# AmbaSat-1_version_2_01.net
KiCad netlist of a schematic drawn in EAGLE
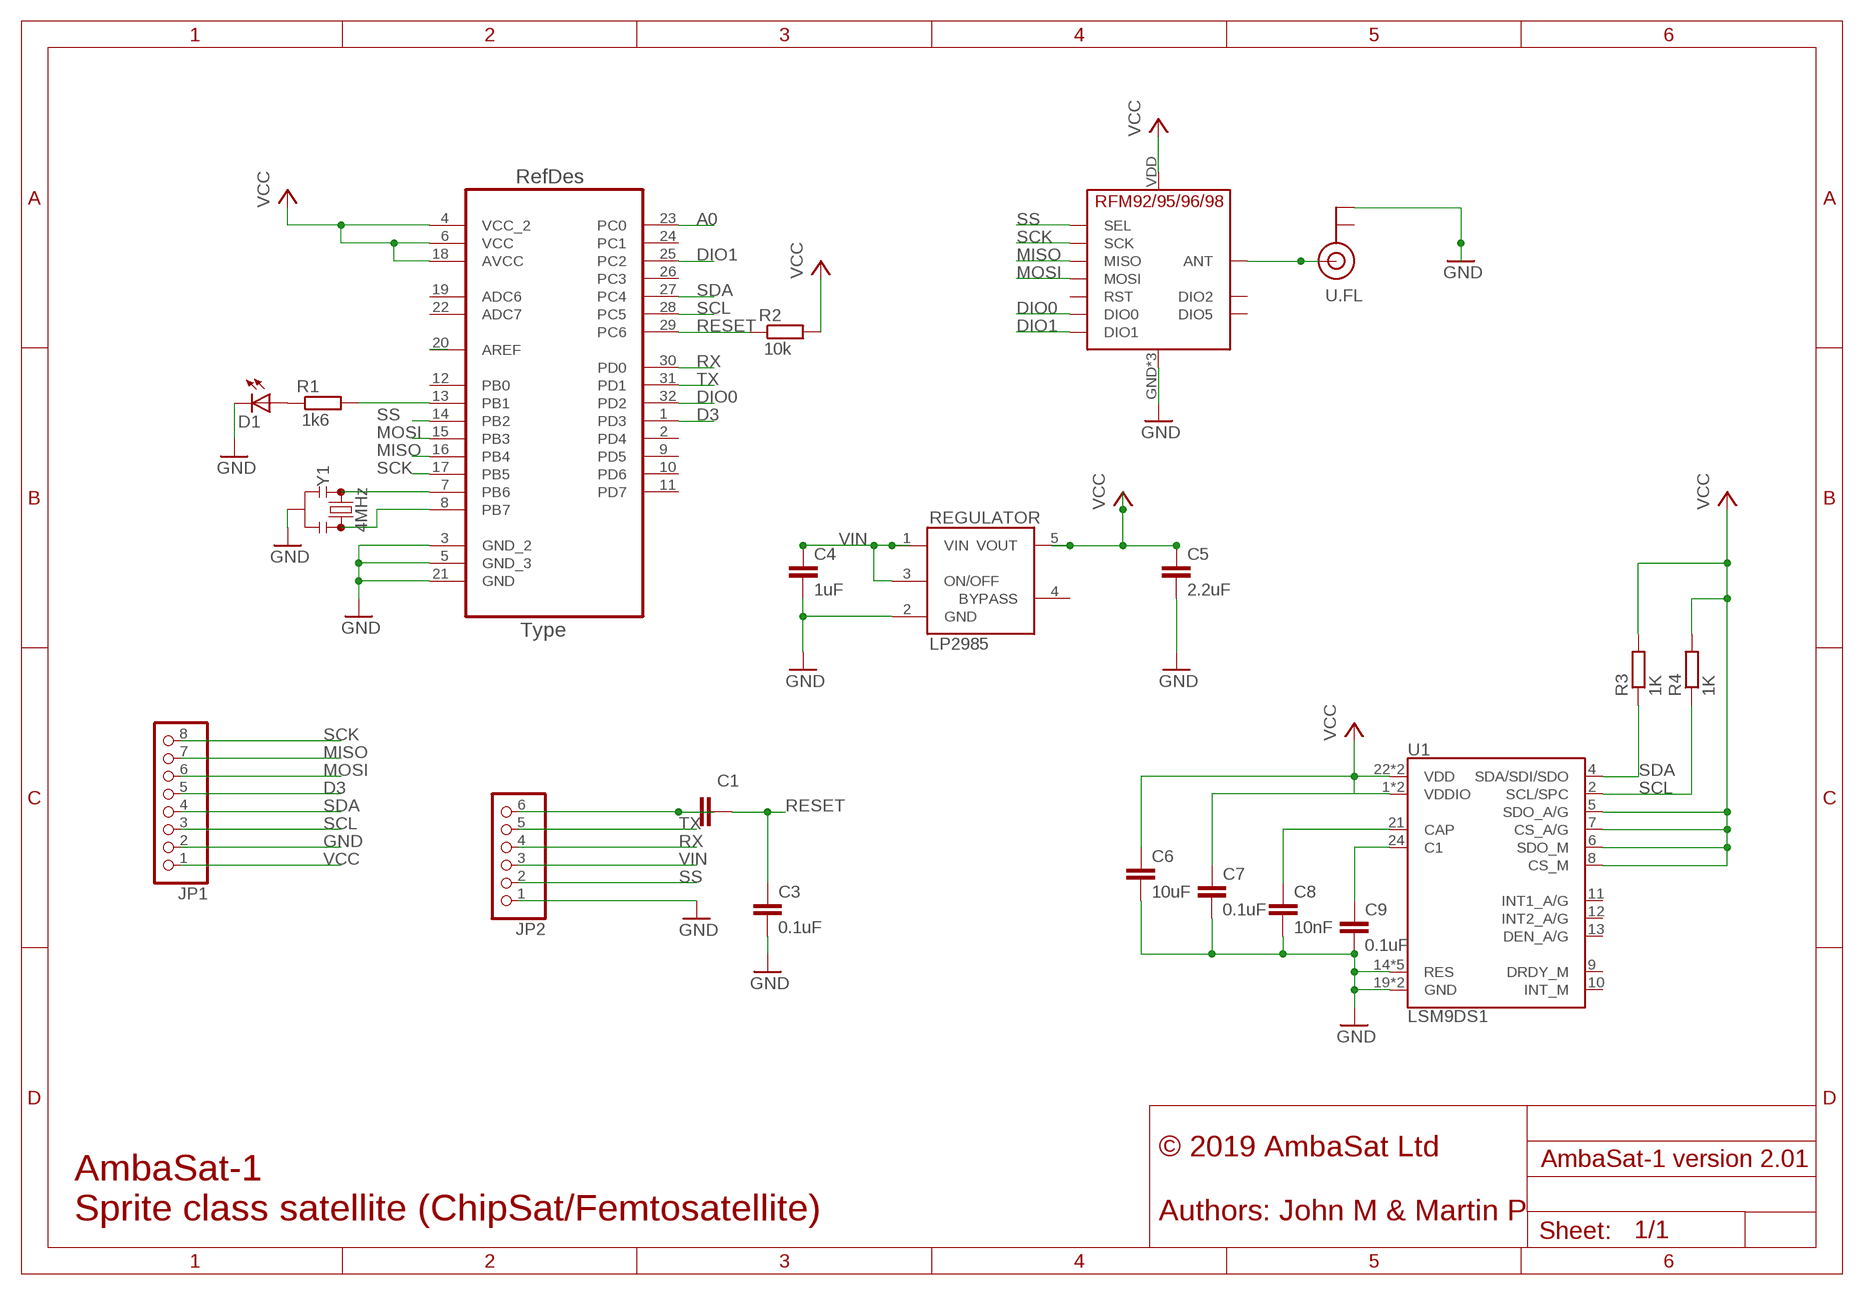
[diagram p0: schematic, sheet 1]

(export (version "E")
  (design (tool "Eeschema 10.0.6"))
  (components
    (comp (ref "ATMEGA328P-AU")
      (value "ATMEGA328P-AU")
      (footprint "eagle-import:QFP80P900X900X120-32N")
      (libsource (lib "eagle-import") (part "ATMEGA328P-AU"))
    )
    (comp (ref "C1")
      (value "1uF")
      (footprint "eagle-import:C0805K")
      (libsource (lib "eagle-import") (part "C-EUC0805K"))
    )
    (comp (ref "C3")
      (value "0.1uF")
      (footprint "eagle-import:C0805K")
      (libsource (lib "eagle-import") (part "C-EUC0805K"))
    )
    (comp (ref "C4")
      (value "1uF")
      (footprint "eagle-import:C0805K")
      (libsource (lib "eagle-import") (part "C-EUC0805K"))
    )
    (comp (ref "C5")
      (value "2.2uF")
      (footprint "eagle-import:C0805K")
      (libsource (lib "eagle-import") (part "C-EUC0805K"))
    )
    (comp (ref "C6")
      (value "10uF")
      (footprint "eagle-import:C0805K")
      (libsource (lib "eagle-import") (part "C-EUC0805K"))
    )
    (comp (ref "C7")
      (value "0.1uF")
      (footprint "eagle-import:C0805K")
      (libsource (lib "eagle-import") (part "C-EUC0805K"))
    )
    (comp (ref "C8")
      (value "10nF")
      (footprint "eagle-import:C0805K")
      (libsource (lib "eagle-import") (part "C-EUC0805K"))
    )
    (comp (ref "C9")
      (value "0.1uF")
      (footprint "eagle-import:C0805K")
      (libsource (lib "eagle-import") (part "C-EUC0805K"))
    )
    (comp (ref "D1")
      (value "LEDCHIP-LED0805")
      (footprint "eagle-import:CHIP-LED0805")
      (libsource (lib "eagle-import") (part "LEDCHIP-LED0805"))
    )
    (comp (ref "JP1")
      (value "PINHD-1X8")
      (footprint "eagle-import:1X08")
      (libsource (lib "eagle-import") (part "PINHD-1X8"))
    )
    (comp (ref "JP2")
      (value "PINHD-1X6")
      (footprint "eagle-import:1X06")
      (libsource (lib "eagle-import") (part "PINHD-1X6"))
    )
    (comp (ref "R1")
      (value "1k6")
      (footprint "eagle-import:M0805")
      (libsource (lib "eagle-import") (part "R-EU_M0805"))
    )
    (comp (ref "R2")
      (value "10k")
      (footprint "eagle-import:M0805")
      (libsource (lib "eagle-import") (part "R-EU_M0805"))
    )
    (comp (ref "R3")
      (value "1K")
      (footprint "eagle-import:M0805")
      (libsource (lib "eagle-import") (part "R-EU_M0805"))
    )
    (comp (ref "R4")
      (value "1K")
      (footprint "eagle-import:M0805")
      (libsource (lib "eagle-import") (part "R-EU_M0805"))
    )
    (comp (ref "REGULATOR")
      (value "LP2985AIM5-3.3")
      (footprint "eagle-import:SOT25")
      (libsource (lib "eagle-import") (part "LP2985AIM5-3.3"))
    )
    (comp (ref "RFM95")
      (value "RFM95")
      (footprint "eagle-import:RFM95")
      (libsource (lib "eagle-import") (part "RFM95"))
    )
    (comp (ref "U.FL")
      (value "U.FL")
      (footprint "eagle-import:U.FL")
      (libsource (lib "eagle-import") (part "U.FL"))
    )
    (comp (ref "U1")
      (value "LSM9DS1")
      (footprint "eagle-import:LGA24-8X4")
      (libsource (lib "eagle-import") (part "LSM9DS1"))
    )
    (comp (ref "Y1")
      (value "4MHz")
      (footprint "eagle-import:RESONATOR-SMD-4.5X2.0")
      (libsource (lib "eagle-import") (part "RESONATOR-4MHZSMD-4.5X2"))
    )
  )
  (nets
    (net (code "1") (name "/A0") (class "Default")
      (node (ref "ATMEGA328P-AU") (pin "23") (pinfunction "PC0_23") (pintype "bidirectional"))
    )
    (net (code "2") (name "/BYPASS") (class "Default")
      (node (ref "REGULATOR") (pin "4") (pinfunction "BYPASS_4") (pintype "power_in"))
    )
    (net (code "3") (name "/D3") (class "Default")
      (node (ref "ATMEGA328P-AU") (pin "1") (pinfunction "PD3_1") (pintype "bidirectional"))
      (node (ref "JP1") (pin "5") (pinfunction "5_5") (pintype "passive"))
    )
    (net (code "4") (name "/DIO0") (class "Default")
      (node (ref "ATMEGA328P-AU") (pin "32") (pinfunction "PD2_32") (pintype "bidirectional"))
      (node (ref "RFM95") (pin "DIO0") (pinfunction "DIO0_DIO0") (pintype "open_collector"))
    )
    (net (code "5") (name "/DIO1") (class "Default")
      (node (ref "ATMEGA328P-AU") (pin "25") (pinfunction "PC2_25") (pintype "bidirectional"))
      (node (ref "RFM95") (pin "DIO1") (pinfunction "DIO1_DIO1") (pintype "open_collector"))
    )
    (net (code "6") (name "/MISO") (class "Default")
      (node (ref "ATMEGA328P-AU") (pin "16") (pinfunction "PB4_16") (pintype "bidirectional"))
      (node (ref "JP1") (pin "7") (pinfunction "7_7") (pintype "passive"))
      (node (ref "RFM95") (pin "MISO") (pinfunction "MISO_MISO") (pintype "input"))
    )
    (net (code "7") (name "/MOSI") (class "Default")
      (node (ref "ATMEGA328P-AU") (pin "15") (pinfunction "PB3_15") (pintype "bidirectional"))
      (node (ref "JP1") (pin "6") (pinfunction "6_6") (pintype "passive"))
      (node (ref "RFM95") (pin "MOSI") (pinfunction "MOSI_MOSI") (pintype "output"))
    )
    (net (code "8") (name "/RESET") (class "Default")
      (node (ref "ATMEGA328P-AU") (pin "29") (pinfunction "PC6_29") (pintype "bidirectional"))
      (node (ref "C1") (pin "1") (pinfunction "1_1") (pintype "passive"))
      (node (ref "C3") (pin "1") (pinfunction "1_1") (pintype "passive"))
      (node (ref "R2") (pin "1") (pinfunction "1_1") (pintype "passive"))
    )
    (net (code "9") (name "/RX") (class "Default")
      (node (ref "ATMEGA328P-AU") (pin "30") (pinfunction "PD0_30") (pintype "bidirectional"))
      (node (ref "JP2") (pin "4") (pinfunction "4_4") (pintype "passive"))
    )
    (net (code "10") (name "/SCK") (class "Default")
      (node (ref "ATMEGA328P-AU") (pin "17") (pinfunction "PB5_17") (pintype "bidirectional"))
      (node (ref "JP1") (pin "8") (pinfunction "8_8") (pintype "passive"))
      (node (ref "RFM95") (pin "SCK") (pinfunction "SCK_SCK") (pintype "input"))
    )
    (net (code "11") (name "/SCL") (class "Default")
      (node (ref "ATMEGA328P-AU") (pin "28") (pinfunction "PC5_28") (pintype "bidirectional"))
      (node (ref "JP1") (pin "3") (pinfunction "3_3") (pintype "passive"))
      (node (ref "R4") (pin "1") (pinfunction "1_1") (pintype "passive"))
      (node (ref "U1") (pin "2") (pinfunction "SCL/SPC_2") (pintype "bidirectional"))
    )
    (net (code "12") (name "/SDA") (class "Default")
      (node (ref "ATMEGA328P-AU") (pin "27") (pinfunction "PC4_27") (pintype "bidirectional"))
      (node (ref "JP1") (pin "4") (pinfunction "4_4") (pintype "passive"))
      (node (ref "R3") (pin "1") (pinfunction "1_1") (pintype "passive"))
      (node (ref "U1") (pin "4") (pinfunction "SDA/SDI/SDO_4") (pintype "bidirectional"))
    )
    (net (code "13") (name "/SS") (class "Default")
      (node (ref "ATMEGA328P-AU") (pin "14") (pinfunction "PB2_14") (pintype "bidirectional"))
      (node (ref "JP2") (pin "2") (pinfunction "2_2") (pintype "passive"))
      (node (ref "RFM95") (pin "NSS") (pinfunction "SEL_NSS") (pintype "input"))
    )
    (net (code "14") (name "/TX") (class "Default")
      (node (ref "ATMEGA328P-AU") (pin "31") (pinfunction "PD1_31") (pintype "bidirectional"))
      (node (ref "JP2") (pin "5") (pinfunction "5_5") (pintype "passive"))
    )
    (net (code "15") (name "/VIN") (class "Default")
      (node (ref "C4") (pin "1") (pinfunction "1_1") (pintype "passive"))
      (node (ref "JP2") (pin "3") (pinfunction "3_3") (pintype "passive"))
      (node (ref "REGULATOR") (pin "1") (pinfunction "VIN_1") (pintype "power_in"))
      (node (ref "REGULATOR") (pin "3") (pinfunction "ON/OFF_3") (pintype "input"))
    )
    (net (code "16") (name "GND") (class "Default")
      (node (ref "ATMEGA328P-AU") (pin "21") (pinfunction "GND_21") (pintype "passive"))
      (node (ref "ATMEGA328P-AU") (pin "3") (pinfunction "GND_2_3") (pintype "passive"))
      (node (ref "ATMEGA328P-AU") (pin "5") (pinfunction "GND_3_5") (pintype "passive"))
      (node (ref "C3") (pin "2") (pinfunction "2_2") (pintype "passive"))
      (node (ref "C4") (pin "2") (pinfunction "2_2") (pintype "passive"))
      (node (ref "C5") (pin "2") (pinfunction "2_2") (pintype "passive"))
      (node (ref "C6") (pin "2") (pinfunction "2_2") (pintype "passive"))
      (node (ref "C7") (pin "2") (pinfunction "2_2") (pintype "passive"))
      (node (ref "C8") (pin "2") (pinfunction "2_2") (pintype "passive"))
      (node (ref "C9") (pin "2") (pinfunction "2_2") (pintype "passive"))
      (node (ref "D1") (pin "C") (pinfunction "C_C") (pintype "passive"))
      (node (ref "JP1") (pin "2") (pinfunction "2_2") (pintype "passive"))
      (node (ref "JP2") (pin "1") (pinfunction "1_1") (pintype "passive"))
      (node (ref "REGULATOR") (pin "2") (pinfunction "GND_2") (pintype "power_in"))
      (node (ref "RFM95") (pin "GND") (pinfunction "GND_GND") (pintype "power_in"))
      (node (ref "RFM95") (pin "GND1") (pinfunction "GND_GND1") (pintype "power_in"))
      (node (ref "RFM95") (pin "GND2") (pinfunction "GND_GND2") (pintype "power_in"))
      (node (ref "U.FL") (pin "2") (pinfunction "GND_2") (pintype "bidirectional"))
      (node (ref "U1") (pin "14") (pinfunction "RES_14") (pintype "bidirectional"))
      (node (ref "U1") (pin "15") (pinfunction "RES_15") (pintype "bidirectional"))
      (node (ref "U1") (pin "16") (pinfunction "RES_16") (pintype "bidirectional"))
      (node (ref "U1") (pin "17") (pinfunction "RES_17") (pintype "bidirectional"))
      (node (ref "U1") (pin "18") (pinfunction "RES_18") (pintype "bidirectional"))
      (node (ref "U1") (pin "19") (pinfunction "GND_19") (pintype "bidirectional"))
      (node (ref "U1") (pin "20") (pinfunction "GND_20") (pintype "bidirectional"))
      (node (ref "Y1") (pin "2") (pinfunction "2_2") (pintype "passive"))
    )
    (net (code "17") (name "Net-(ATMEGA328P-AU-PB1)") (class "Default")
      (node (ref "ATMEGA328P-AU") (pin "13") (pinfunction "PB1_13") (pintype "bidirectional"))
      (node (ref "R1") (pin "2") (pinfunction "2_2") (pintype "passive"))
    )
    (net (code "18") (name "Net-(ATMEGA328P-AU-PB6)") (class "Default")
      (node (ref "ATMEGA328P-AU") (pin "7") (pinfunction "PB6_7") (pintype "bidirectional"))
      (node (ref "Y1") (pin "1") (pinfunction "1_1") (pintype "passive"))
    )
    (net (code "19") (name "Net-(ATMEGA328P-AU-PB7)") (class "Default")
      (node (ref "ATMEGA328P-AU") (pin "8") (pinfunction "PB7_8") (pintype "bidirectional"))
      (node (ref "Y1") (pin "3") (pinfunction "3_3") (pintype "passive"))
    )
    (net (code "20") (name "Net-(C1-Pad2)") (class "Default")
      (node (ref "C1") (pin "2") (pinfunction "2_2") (pintype "passive"))
      (node (ref "JP2") (pin "6") (pinfunction "6_6") (pintype "passive"))
    )
    (net (code "21") (name "Net-(D1-PadA)") (class "Default")
      (node (ref "D1") (pin "A") (pinfunction "A_A") (pintype "passive"))
      (node (ref "R1") (pin "1") (pinfunction "1_1") (pintype "passive"))
    )
    (net (code "22") (name "Net-(U.FL-SIGNAL)") (class "Default")
      (node (ref "RFM95") (pin "ANT") (pinfunction "ANT_ANT") (pintype "passive"))
      (node (ref "U.FL") (pin "FEED") (pinfunction "SIGNAL_FEED") (pintype "bidirectional"))
    )
    (net (code "23") (name "Net-(U1-C1)") (class "Default")
      (node (ref "C9") (pin "1") (pinfunction "1_1") (pintype "passive"))
      (node (ref "U1") (pin "24") (pinfunction "C1_24") (pintype "bidirectional"))
    )
    (net (code "24") (name "Net-(U1-CAP)") (class "Default")
      (node (ref "C8") (pin "1") (pinfunction "1_1") (pintype "passive"))
      (node (ref "U1") (pin "21") (pinfunction "CAP_21") (pintype "bidirectional"))
    )
    (net (code "25") (name "VCC") (class "Default")
      (node (ref "ATMEGA328P-AU") (pin "18") (pinfunction "AVCC_18") (pintype "power_in"))
      (node (ref "ATMEGA328P-AU") (pin "4") (pinfunction "VCC_2_4") (pintype "power_in"))
      (node (ref "ATMEGA328P-AU") (pin "6") (pinfunction "VCC_6") (pintype "power_in"))
      (node (ref "C5") (pin "1") (pinfunction "1_1") (pintype "passive"))
      (node (ref "C6") (pin "1") (pinfunction "1_1") (pintype "passive"))
      (node (ref "C7") (pin "1") (pinfunction "1_1") (pintype "passive"))
      (node (ref "JP1") (pin "1") (pinfunction "1_1") (pintype "passive"))
      (node (ref "R2") (pin "2") (pinfunction "2_2") (pintype "passive"))
      (node (ref "R3") (pin "2") (pinfunction "2_2") (pintype "passive"))
      (node (ref "R4") (pin "2") (pinfunction "2_2") (pintype "passive"))
      (node (ref "REGULATOR") (pin "5") (pinfunction "VOUT_5") (pintype "power_in"))
      (node (ref "RFM95") (pin "VDD") (pinfunction "VCC_VDD") (pintype "power_in"))
      (node (ref "U1") (pin "1") (pinfunction "VDDIO_1") (pintype "bidirectional"))
      (node (ref "U1") (pin "22") (pinfunction "VDD_22") (pintype "bidirectional"))
      (node (ref "U1") (pin "23") (pinfunction "VDD_23") (pintype "bidirectional"))
      (node (ref "U1") (pin "3") (pinfunction "VDDIO_3") (pintype "bidirectional"))
      (node (ref "U1") (pin "5") (pinfunction "SDO_A/G_5") (pintype "bidirectional"))
      (node (ref "U1") (pin "6") (pinfunction "SDO_M_6") (pintype "bidirectional"))
      (node (ref "U1") (pin "7") (pinfunction "CS_A/G_7") (pintype "bidirectional"))
      (node (ref "U1") (pin "8") (pinfunction "CS_M_8") (pintype "bidirectional"))
    )
    (net (code "26") (name "unconnected-(ATMEGA328P-AU-ADC6-Pad19)") (class "Default")
      (node (ref "ATMEGA328P-AU") (pin "19") (pinfunction "ADC6_19") (pintype "input"))
    )
    (net (code "27") (name "unconnected-(ATMEGA328P-AU-ADC7-Pad22)") (class "Default")
      (node (ref "ATMEGA328P-AU") (pin "22") (pinfunction "ADC7_22") (pintype "input"))
    )
    (net (code "28") (name "unconnected-(ATMEGA328P-AU-AREF-Pad20)") (class "Default")
      (node (ref "ATMEGA328P-AU") (pin "20") (pinfunction "AREF_20") (pintype "input"))
    )
    (net (code "29") (name "unconnected-(ATMEGA328P-AU-PB0-Pad12)") (class "Default")
      (node (ref "ATMEGA328P-AU") (pin "12") (pinfunction "PB0_12") (pintype "bidirectional"))
    )
    (net (code "30") (name "unconnected-(ATMEGA328P-AU-PC1-Pad24)") (class "Default")
      (node (ref "ATMEGA328P-AU") (pin "24") (pinfunction "PC1_24") (pintype "bidirectional"))
    )
    (net (code "31") (name "unconnected-(ATMEGA328P-AU-PC3-Pad26)") (class "Default")
      (node (ref "ATMEGA328P-AU") (pin "26") (pinfunction "PC3_26") (pintype "bidirectional"))
    )
    (net (code "32") (name "unconnected-(ATMEGA328P-AU-PD4-Pad2)") (class "Default")
      (node (ref "ATMEGA328P-AU") (pin "2") (pinfunction "PD4_2") (pintype "bidirectional"))
    )
    (net (code "33") (name "unconnected-(ATMEGA328P-AU-PD5-Pad9)") (class "Default")
      (node (ref "ATMEGA328P-AU") (pin "9") (pinfunction "PD5_9") (pintype "bidirectional"))
    )
    (net (code "34") (name "unconnected-(ATMEGA328P-AU-PD6-Pad10)") (class "Default")
      (node (ref "ATMEGA328P-AU") (pin "10") (pinfunction "PD6_10") (pintype "bidirectional"))
    )
    (net (code "35") (name "unconnected-(ATMEGA328P-AU-PD7-Pad11)") (class "Default")
      (node (ref "ATMEGA328P-AU") (pin "11") (pinfunction "PD7_11") (pintype "bidirectional"))
    )
    (net (code "36") (name "unconnected-(RFM95-PadDIO2)") (class "Default")
      (node (ref "RFM95") (pin "DIO2") (pinfunction "DIO2_DIO2") (pintype "open_collector"))
    )
    (net (code "37") (name "unconnected-(RFM95-PadDIO5)") (class "Default")
      (node (ref "RFM95") (pin "DIO5") (pinfunction "DIO5_DIO5") (pintype "open_collector"))
    )
    (net (code "38") (name "unconnected-(RFM95-PadRST)") (class "Default")
      (node (ref "RFM95") (pin "RST") (pinfunction "RST_RST") (pintype "open_collector"))
    )
    (net (code "39") (name "unconnected-(U.FL-GND-Pad1)") (class "Default")
      (node (ref "U.FL") (pin "1") (pinfunction "GND_1") (pintype "bidirectional"))
    )
    (net (code "40") (name "unconnected-(U1-DEN_A{slash}G-Pad13)") (class "Default")
      (node (ref "U1") (pin "13") (pinfunction "DEN_A/G_13") (pintype "bidirectional"))
    )
    (net (code "41") (name "unconnected-(U1-DRDY_M-Pad9)") (class "Default")
      (node (ref "U1") (pin "9") (pinfunction "DRDY_M_9") (pintype "bidirectional"))
    )
    (net (code "42") (name "unconnected-(U1-INT1_A{slash}G-Pad11)") (class "Default")
      (node (ref "U1") (pin "11") (pinfunction "INT1_A/G_11") (pintype "bidirectional"))
    )
    (net (code "43") (name "unconnected-(U1-INT2_A{slash}G-Pad12)") (class "Default")
      (node (ref "U1") (pin "12") (pinfunction "INT2_A/G_12") (pintype "bidirectional"))
    )
    (net (code "44") (name "unconnected-(U1-INT_M-Pad10)") (class "Default")
      (node (ref "U1") (pin "10") (pinfunction "INT_M_10") (pintype "bidirectional"))
    )
  )
)
